# R002X.net
KiCad netlist of a schematic drawn in EAGLE
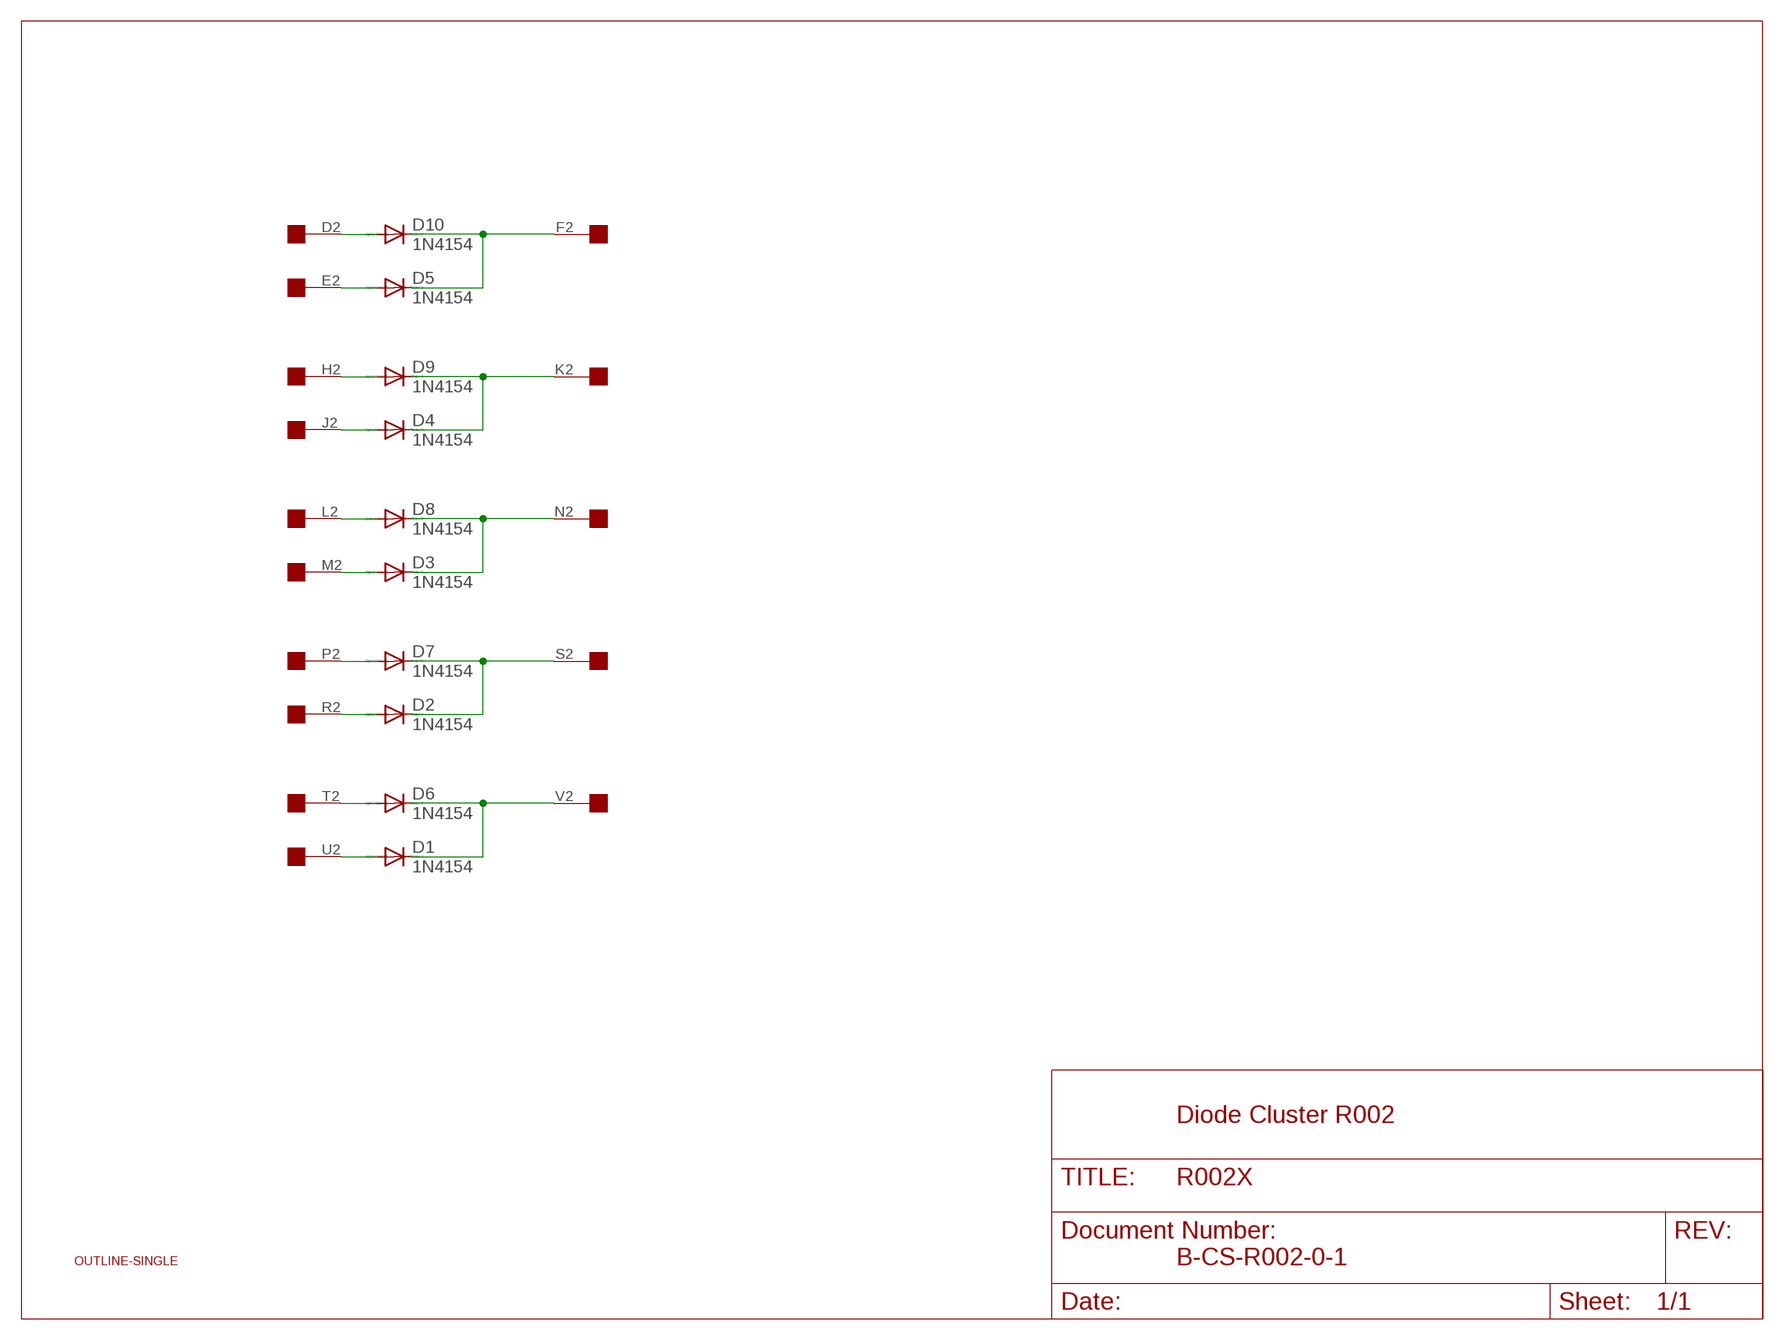
[diagram p0: schematic, sheet 1]

(export (version "E")
  (design (tool "Eeschema 10.0.6"))
  (components
    (comp (ref "D1")
      (value "1N4154")
      (footprint "eagle-import:DO35-10")
      (libsource (lib "eagle-import") (part "1N4148DO35-10"))
    )
    (comp (ref "D2")
      (value "1N4154")
      (footprint "eagle-import:DO35-10")
      (libsource (lib "eagle-import") (part "1N4148DO35-10"))
    )
    (comp (ref "D3")
      (value "1N4154")
      (footprint "eagle-import:DO35-10")
      (libsource (lib "eagle-import") (part "1N4148DO35-10"))
    )
    (comp (ref "D4")
      (value "1N4154")
      (footprint "eagle-import:DO35-10")
      (libsource (lib "eagle-import") (part "1N4148DO35-10"))
    )
    (comp (ref "D5")
      (value "1N4154")
      (footprint "eagle-import:DO35-10")
      (libsource (lib "eagle-import") (part "1N4148DO35-10"))
    )
    (comp (ref "D6")
      (value "1N4154")
      (footprint "eagle-import:DO35-10")
      (libsource (lib "eagle-import") (part "1N4148DO35-10"))
    )
    (comp (ref "D7")
      (value "1N4154")
      (footprint "eagle-import:DO35-10")
      (libsource (lib "eagle-import") (part "1N4148DO35-10"))
    )
    (comp (ref "D8")
      (value "1N4154")
      (footprint "eagle-import:DO35-10")
      (libsource (lib "eagle-import") (part "1N4148DO35-10"))
    )
    (comp (ref "D9")
      (value "1N4154")
      (footprint "eagle-import:DO35-10")
      (libsource (lib "eagle-import") (part "1N4148DO35-10"))
    )
    (comp (ref "D10")
      (value "1N4154")
      (footprint "eagle-import:DO35-10")
      (libsource (lib "eagle-import") (part "1N4148DO35-10"))
    )
    (comp (ref "U$1")
      (value "OUTLINE-SINGLE")
      (footprint "eagle-import:SINGLE")
      (libsource (lib "eagle-import") (part "OUTLINE-SINGLE"))
    )
    (comp (ref "U$2")
      (value "EDGE-1")
      (footprint "eagle-import:EDGE-CON1")
      (libsource (lib "eagle-import") (part "EDGE-1"))
    )
  )
  (nets
    (net (code "1") (name "Net-(U$2D-1)") (class "Default")
      (node (ref "D10") (pin "A") (pinfunction "A_A") (pintype "passive"))
      (node (ref "U$2") (pin "D2") (pinfunction "1_D2") (pintype "bidirectional"))
    )
    (net (code "2") (name "Net-(U$2E-1)") (class "Default")
      (node (ref "D5") (pin "A") (pinfunction "A_A") (pintype "passive"))
      (node (ref "U$2") (pin "E2") (pinfunction "1_E2") (pintype "bidirectional"))
    )
    (net (code "3") (name "Net-(U$2F-1)") (class "Default")
      (node (ref "D10") (pin "C") (pinfunction "C_C") (pintype "passive"))
      (node (ref "D5") (pin "C") (pinfunction "C_C") (pintype "passive"))
      (node (ref "U$2") (pin "F2") (pinfunction "1_F2") (pintype "bidirectional"))
    )
    (net (code "4") (name "Net-(U$2G-1)") (class "Default")
      (node (ref "D9") (pin "A") (pinfunction "A_A") (pintype "passive"))
      (node (ref "U$2") (pin "H2") (pinfunction "1_H2") (pintype "bidirectional"))
    )
    (net (code "5") (name "Net-(U$2H-1)") (class "Default")
      (node (ref "D4") (pin "A") (pinfunction "A_A") (pintype "passive"))
      (node (ref "U$2") (pin "J2") (pinfunction "1_J2") (pintype "bidirectional"))
    )
    (net (code "6") (name "Net-(U$2I-1)") (class "Default")
      (node (ref "D4") (pin "C") (pinfunction "C_C") (pintype "passive"))
      (node (ref "D9") (pin "C") (pinfunction "C_C") (pintype "passive"))
      (node (ref "U$2") (pin "K2") (pinfunction "1_K2") (pintype "bidirectional"))
    )
    (net (code "7") (name "Net-(U$2J-1)") (class "Default")
      (node (ref "D8") (pin "A") (pinfunction "A_A") (pintype "passive"))
      (node (ref "U$2") (pin "L2") (pinfunction "1_L2") (pintype "bidirectional"))
    )
    (net (code "8") (name "Net-(U$2K-1)") (class "Default")
      (node (ref "D3") (pin "A") (pinfunction "A_A") (pintype "passive"))
      (node (ref "U$2") (pin "M2") (pinfunction "1_M2") (pintype "bidirectional"))
    )
    (net (code "9") (name "Net-(U$2L-1)") (class "Default")
      (node (ref "D3") (pin "C") (pinfunction "C_C") (pintype "passive"))
      (node (ref "D8") (pin "C") (pinfunction "C_C") (pintype "passive"))
      (node (ref "U$2") (pin "N2") (pinfunction "1_N2") (pintype "bidirectional"))
    )
    (net (code "10") (name "Net-(U$2M-1)") (class "Default")
      (node (ref "D7") (pin "A") (pinfunction "A_A") (pintype "passive"))
      (node (ref "U$2") (pin "P2") (pinfunction "1_P2") (pintype "bidirectional"))
    )
    (net (code "11") (name "Net-(U$2N-1)") (class "Default")
      (node (ref "D2") (pin "A") (pinfunction "A_A") (pintype "passive"))
      (node (ref "U$2") (pin "R2") (pinfunction "1_R2") (pintype "bidirectional"))
    )
    (net (code "12") (name "Net-(U$2O-1)") (class "Default")
      (node (ref "D2") (pin "C") (pinfunction "C_C") (pintype "passive"))
      (node (ref "D7") (pin "C") (pinfunction "C_C") (pintype "passive"))
      (node (ref "U$2") (pin "S2") (pinfunction "1_S2") (pintype "bidirectional"))
    )
    (net (code "13") (name "Net-(U$2P-1)") (class "Default")
      (node (ref "D6") (pin "A") (pinfunction "A_A") (pintype "passive"))
      (node (ref "U$2") (pin "T2") (pinfunction "1_T2") (pintype "bidirectional"))
    )
    (net (code "14") (name "Net-(U$2Q-1)") (class "Default")
      (node (ref "D1") (pin "A") (pinfunction "A_A") (pintype "passive"))
      (node (ref "U$2") (pin "U2") (pinfunction "1_U2") (pintype "bidirectional"))
    )
    (net (code "15") (name "Net-(U$2R-1)") (class "Default")
      (node (ref "D1") (pin "C") (pinfunction "C_C") (pintype "passive"))
      (node (ref "D6") (pin "C") (pinfunction "C_C") (pintype "passive"))
      (node (ref "U$2") (pin "V2") (pinfunction "1_V2") (pintype "bidirectional"))
    )
  )
)
